# 5V_LD1117S50CTR.net
KiCad netlist of a schematic drawn in Altium Designer
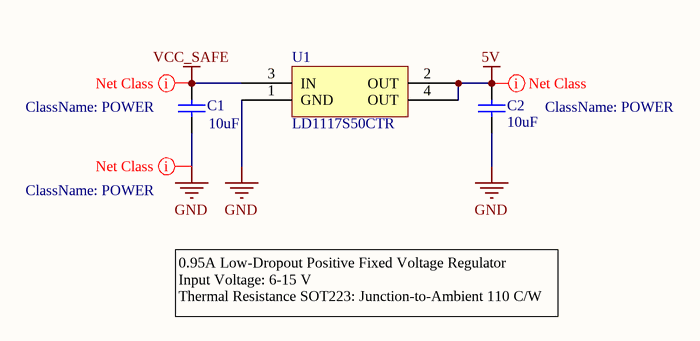
[diagram p0: 5V LD1117S50CTR.SchDoc]

(export (version "E")
  (design (tool "Eeschema 10.0.6"))
  (components
    (comp (ref "C1")
      (value "10uF")
      (footprint "agh_racing_2018:CAP_0603_IPC_MD")
      (description "Capacitor")
      (fields (field (name "Comment") "Cap"))
      (libsource (lib "agh_racing_2018") (part "Cap"))
    )
    (comp (ref "C2")
      (value "10uF")
      (footprint "agh_racing_2018:CAP_0603_IPC_MD")
      (description "Capacitor")
      (fields (field (name "Comment") "Cap"))
      (libsource (lib "agh_racing_2018") (part "Cap"))
    )
    (comp (ref "U1")
      (value "LD1117S50CTR")
      (footprint "SOT223_IPC_MD")
      (fields (field (name "MANUFACTURER") "ST Microelectronics"))
      (libsource (lib "agh_racing_2018") (part "LDO"))
    )
  )
  (nets
    (net (code "1") (name "5V") (class "Default")
      (node (ref "C2") (pin "2") (pinfunction "2_2") (pintype "passive"))
      (node (ref "U1") (pin "2") (pinfunction "OUT_2") (pintype "power_in"))
      (node (ref "U1") (pin "4") (pinfunction "OUT_4") (pintype "power_in"))
    )
    (net (code "2") (name "GND") (class "Default")
      (node (ref "C1") (pin "1") (pinfunction "1_1") (pintype "passive"))
      (node (ref "C2") (pin "1") (pinfunction "1_1") (pintype "passive"))
      (node (ref "U1") (pin "1") (pinfunction "GND_1") (pintype "power_in"))
    )
    (net (code "3") (name "VCC_SAFE") (class "Default")
      (node (ref "C1") (pin "2") (pinfunction "2_2") (pintype "passive"))
      (node (ref "U1") (pin "3") (pinfunction "IN_3") (pintype "power_in"))
    )
  )
)
